# tx_board.net
KiCad netlist of a schematic drawn in EAGLE
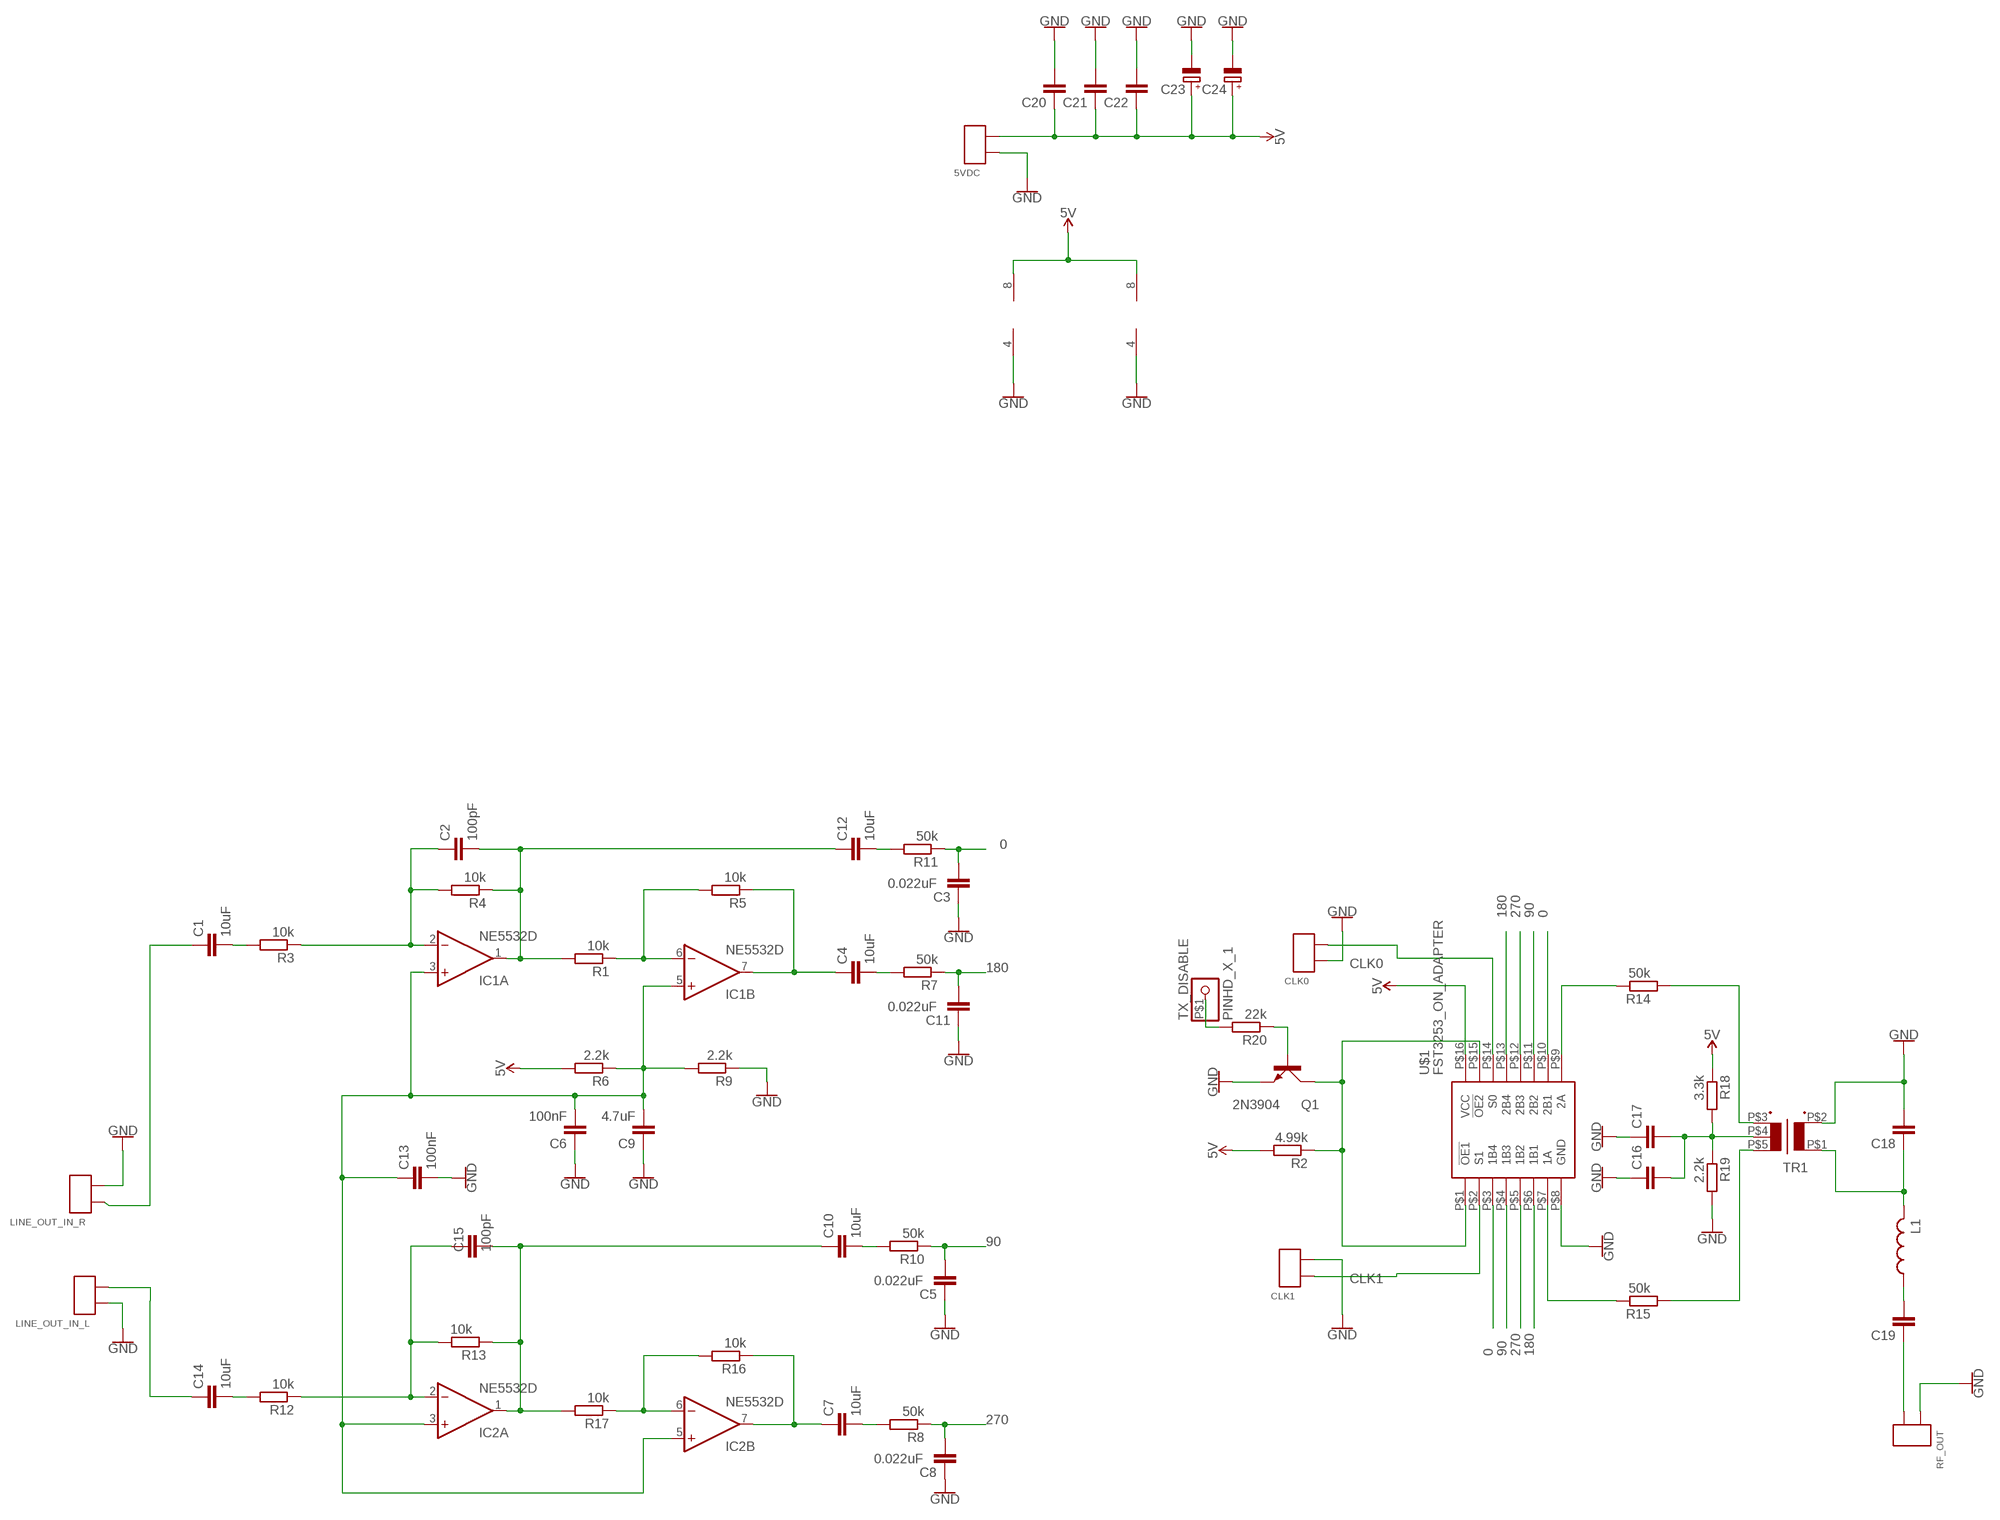
[diagram p0: schematic, sheet 1]

(export (version "E")
  (design (tool "Eeschema 10.0.6"))
  (components
    (comp (ref "5VDC")
      (value "2X_SMD_PTH_PIN")
      (footprint "eagle-import:2X_SMD_PTH")
      (libsource (lib "eagle-import") (part "2X_SMD_PTH_PIN"))
    )
    (comp (ref "C1")
      (value "10uF")
      (footprint "eagle-import:C0805K")
      (libsource (lib "eagle-import") (part "C_0805_PTH"))
    )
    (comp (ref "C2")
      (value "100pF")
      (footprint "eagle-import:C0805K")
      (libsource (lib "eagle-import") (part "C_0805_PTH"))
    )
    (comp (ref "C3")
      (value "0.022uF")
      (footprint "eagle-import:C0805")
      (libsource (lib "eagle-import") (part "C_0805_SMD"))
    )
    (comp (ref "C4")
      (value "10uF")
      (footprint "eagle-import:C0805K")
      (libsource (lib "eagle-import") (part "C_0805_PTH"))
    )
    (comp (ref "C5")
      (value "0.022uF")
      (footprint "eagle-import:C0805")
      (libsource (lib "eagle-import") (part "C_0805_SMD"))
    )
    (comp (ref "C6")
      (value "100nF")
      (footprint "eagle-import:C0805")
      (libsource (lib "eagle-import") (part "C_0805_SMD"))
    )
    (comp (ref "C7")
      (value "10uF")
      (footprint "eagle-import:C0805K")
      (libsource (lib "eagle-import") (part "C_0805_PTH"))
    )
    (comp (ref "C8")
      (value "0.022uF")
      (footprint "eagle-import:C0805")
      (libsource (lib "eagle-import") (part "C_0805_SMD"))
    )
    (comp (ref "C9")
      (value "4.7uF")
      (footprint "eagle-import:C0805")
      (libsource (lib "eagle-import") (part "C_0805_SMD"))
    )
    (comp (ref "C10")
      (value "10uF")
      (footprint "eagle-import:C0805K")
      (libsource (lib "eagle-import") (part "C_0805_PTH"))
    )
    (comp (ref "C11")
      (value "0.022uF")
      (footprint "eagle-import:C0805")
      (libsource (lib "eagle-import") (part "C_0805_SMD"))
    )
    (comp (ref "C12")
      (value "10uF")
      (footprint "eagle-import:C0805K")
      (libsource (lib "eagle-import") (part "C_0805_PTH"))
    )
    (comp (ref "C13")
      (value "100nF")
      (footprint "eagle-import:C0805")
      (libsource (lib "eagle-import") (part "C_0805_SMD"))
    )
    (comp (ref "C14")
      (value "10uF")
      (footprint "eagle-import:C0805K")
      (libsource (lib "eagle-import") (part "C_0805_PTH"))
    )
    (comp (ref "C15")
      (value "100pF")
      (footprint "eagle-import:C0805K")
      (libsource (lib "eagle-import") (part "C_0805_PTH"))
    )
    (comp (ref "C16")
      (value "C_0805_SMD")
      (footprint "eagle-import:C0805")
      (libsource (lib "eagle-import") (part "C_0805_SMD"))
    )
    (comp (ref "C17")
      (value "C_0805_PTH")
      (footprint "eagle-import:C0805K")
      (libsource (lib "eagle-import") (part "C_0805_PTH"))
    )
    (comp (ref "C18")
      (value "C_0805_PTH")
      (footprint "eagle-import:C0805K")
      (libsource (lib "eagle-import") (part "C_0805_PTH"))
    )
    (comp (ref "C19")
      (value "C_0805_PTH")
      (footprint "eagle-import:C0805K")
      (libsource (lib "eagle-import") (part "C_0805_PTH"))
    )
    (comp (ref "C20")
      (value "C_0805_SMD")
      (footprint "eagle-import:C0805")
      (libsource (lib "eagle-import") (part "C_0805_SMD"))
    )
    (comp (ref "C21")
      (value "C_0805_SMD")
      (footprint "eagle-import:C0805")
      (libsource (lib "eagle-import") (part "C_0805_SMD"))
    )
    (comp (ref "C22")
      (value "C_0805_SMD")
      (footprint "eagle-import:C0805")
      (libsource (lib "eagle-import") (part "C_0805_SMD"))
    )
    (comp (ref "C23")
      (value "C_POL")
      (footprint "eagle-import:E5-5")
      (libsource (lib "eagle-import") (part "C_POL"))
    )
    (comp (ref "C24")
      (value "C_POL")
      (footprint "eagle-import:E5-5")
      (libsource (lib "eagle-import") (part "C_POL"))
    )
    (comp (ref "CLK0")
      (value "2X_SMD_PTH_PIN")
      (footprint "eagle-import:2X_SMD_PTH")
      (libsource (lib "eagle-import") (part "2X_SMD_PTH_PIN"))
    )
    (comp (ref "CLK1")
      (value "2X_SMD_PTH_PIN")
      (footprint "eagle-import:2X_SMD_PTH")
      (libsource (lib "eagle-import") (part "2X_SMD_PTH_PIN"))
    )
    (comp (ref "IC1")
      (value "NE5532D")
      (footprint "eagle-import:SO08")
      (libsource (lib "eagle-import") (part "NE5532D"))
    )
    (comp (ref "IC2")
      (value "NE5532D")
      (footprint "eagle-import:SO08")
      (libsource (lib "eagle-import") (part "NE5532D"))
    )
    (comp (ref "L1")
      (value "L_0805_PTH")
      (footprint "eagle-import:M0805")
      (libsource (lib "eagle-import") (part "L_0805_PTH"))
    )
    (comp (ref "LINE_OUT_IN_L")
      (value "2X_SMD_PTH_PIN")
      (footprint "eagle-import:2X_SMD_PTH")
      (libsource (lib "eagle-import") (part "2X_SMD_PTH_PIN"))
    )
    (comp (ref "LINE_OUT_IN_R")
      (value "2X_SMD_PTH_PIN")
      (footprint "eagle-import:2X_SMD_PTH")
      (libsource (lib "eagle-import") (part "2X_SMD_PTH_PIN"))
    )
    (comp (ref "Q1")
      (value "2N3904")
      (footprint "eagle-import:TO92D")
      (libsource (lib "eagle-import") (part "2N3904"))
    )
    (comp (ref "R1")
      (value "10k")
      (footprint "eagle-import:R0805")
      (libsource (lib "eagle-import") (part "R_0805_PTH"))
    )
    (comp (ref "R2")
      (value "4.99k")
      (footprint "eagle-import:R0805W")
      (libsource (lib "eagle-import") (part "R_0805_SMD"))
    )
    (comp (ref "R3")
      (value "10k")
      (footprint "eagle-import:R0805")
      (libsource (lib "eagle-import") (part "R_0805_PTH"))
    )
    (comp (ref "R4")
      (value "10k")
      (footprint "eagle-import:R0805")
      (libsource (lib "eagle-import") (part "R_0805_PTH"))
    )
    (comp (ref "R5")
      (value "10k")
      (footprint "eagle-import:R0805W")
      (libsource (lib "eagle-import") (part "R_0805_SMD"))
    )
    (comp (ref "R6")
      (value "2.2k")
      (footprint "eagle-import:0204_7")
      (libsource (lib "eagle-import") (part "R-EU_0204/7"))
    )
    (comp (ref "R7")
      (value "50k")
      (footprint "eagle-import:R0805")
      (libsource (lib "eagle-import") (part "R_0805_PTH"))
    )
    (comp (ref "R8")
      (value "50k")
      (footprint "eagle-import:R0805")
      (libsource (lib "eagle-import") (part "R_0805_PTH"))
    )
    (comp (ref "R9")
      (value "2.2k")
      (footprint "eagle-import:R0805W")
      (libsource (lib "eagle-import") (part "R_0805_SMD"))
    )
    (comp (ref "R10")
      (value "50k")
      (footprint "eagle-import:R0805")
      (libsource (lib "eagle-import") (part "R_0805_PTH"))
    )
    (comp (ref "R11")
      (value "50k")
      (footprint "eagle-import:R0805")
      (libsource (lib "eagle-import") (part "R_0805_PTH"))
    )
    (comp (ref "R12")
      (value "10k")
      (footprint "eagle-import:R0805")
      (libsource (lib "eagle-import") (part "R_0805_PTH"))
    )
    (comp (ref "R13")
      (value "10k")
      (footprint "eagle-import:R0805")
      (libsource (lib "eagle-import") (part "R_0805_PTH"))
    )
    (comp (ref "R14")
      (value "50k")
      (footprint "eagle-import:R0805")
      (libsource (lib "eagle-import") (part "R_0805_PTH"))
    )
    (comp (ref "R15")
      (value "50k")
      (footprint "eagle-import:R0805")
      (libsource (lib "eagle-import") (part "R_0805_PTH"))
    )
    (comp (ref "R16")
      (value "10k")
      (footprint "eagle-import:R0805")
      (libsource (lib "eagle-import") (part "R_0805_PTH"))
    )
    (comp (ref "R17")
      (value "10k")
      (footprint "eagle-import:R0805W")
      (libsource (lib "eagle-import") (part "R_0805_SMD"))
    )
    (comp (ref "R18")
      (value "3.3k")
      (footprint "eagle-import:R0805W")
      (libsource (lib "eagle-import") (part "R_0805_SMD"))
    )
    (comp (ref "R19")
      (value "2.2k")
      (footprint "eagle-import:R0805W")
      (libsource (lib "eagle-import") (part "R_0805_SMD"))
    )
    (comp (ref "R20")
      (value "22k")
      (footprint "eagle-import:R0805W")
      (libsource (lib "eagle-import") (part "R_0805_SMD"))
    )
    (comp (ref "RF_OUT")
      (value "2X_SMD_PTH_PIN")
      (footprint "eagle-import:2X_SMD_PTH")
      (libsource (lib "eagle-import") (part "2X_SMD_PTH_PIN"))
    )
    (comp (ref "TR1")
      (value "5PIN_TRANSFORMER")
      (footprint "eagle-import:5PIN_TRANSFORMER")
      (libsource (lib "eagle-import") (part "5PIN_TRANSFORMER"))
    )
    (comp (ref "TX_DISABLE")
      (value "PINHD_X_1")
      (footprint "eagle-import:PINHD1")
      (libsource (lib "eagle-import") (part "PINHD_X_1"))
    )
    (comp (ref "U$1")
      (value "FST3253_ON_ADAPTER")
      (footprint "eagle-import:SSOP16_ADAPTER")
      (libsource (lib "eagle-import") (part "FST3253_ON_ADAPTER"))
    )
  )
  (nets
    (net (code "1") (name "/0") (class "Default")
      (node (ref "C3") (pin "2") (pinfunction "2_2") (pintype "passive"))
      (node (ref "R11") (pin "1") (pinfunction "1_1") (pintype "passive"))
      (node (ref "R11") (pin "P$1") (pinfunction "1_P$1") (pintype "passive"))
      (node (ref "U$1") (pin "P$10") (pinfunction "2B1_P$10") (pintype "bidirectional"))
      (node (ref "U$1") (pin "P$3") (pinfunction "1B4_P$3") (pintype "bidirectional"))
    )
    (net (code "2") (name "/90") (class "Default")
      (node (ref "C5") (pin "2") (pinfunction "2_2") (pintype "passive"))
      (node (ref "R10") (pin "1") (pinfunction "1_1") (pintype "passive"))
      (node (ref "R10") (pin "P$1") (pinfunction "1_P$1") (pintype "passive"))
      (node (ref "U$1") (pin "P$11") (pinfunction "2B2_P$11") (pintype "bidirectional"))
      (node (ref "U$1") (pin "P$4") (pinfunction "1B3_P$4") (pintype "bidirectional"))
    )
    (net (code "3") (name "/180") (class "Default")
      (node (ref "C11") (pin "2") (pinfunction "2_2") (pintype "passive"))
      (node (ref "R7") (pin "1") (pinfunction "1_1") (pintype "passive"))
      (node (ref "R7") (pin "P$1") (pinfunction "1_P$1") (pintype "passive"))
      (node (ref "U$1") (pin "P$13") (pinfunction "2B4_P$13") (pintype "bidirectional"))
      (node (ref "U$1") (pin "P$6") (pinfunction "1B1_P$6") (pintype "bidirectional"))
    )
    (net (code "4") (name "/270") (class "Default")
      (node (ref "C8") (pin "2") (pinfunction "2_2") (pintype "passive"))
      (node (ref "R8") (pin "1") (pinfunction "1_1") (pintype "passive"))
      (node (ref "R8") (pin "P$1") (pinfunction "1_P$1") (pintype "passive"))
      (node (ref "U$1") (pin "P$12") (pinfunction "2B3_P$12") (pintype "bidirectional"))
      (node (ref "U$1") (pin "P$5") (pinfunction "1B2_P$5") (pintype "bidirectional"))
    )
    (net (code "5") (name "/CLK0") (class "Default")
      (node (ref "CLK0") (pin "P$2") (pinfunction "PIN1_P$2") (pintype "bidirectional"))
      (node (ref "CLK0") (pin "T$2") (pinfunction "PIN1_T$2") (pintype "bidirectional"))
      (node (ref "U$1") (pin "P$14") (pinfunction "S0_P$14") (pintype "bidirectional"))
    )
    (net (code "6") (name "/CLK1") (class "Default")
      (node (ref "CLK1") (pin "P$1") (pinfunction "PIN0_P$1") (pintype "bidirectional"))
      (node (ref "CLK1") (pin "T$1") (pinfunction "PIN0_T$1") (pintype "bidirectional"))
      (node (ref "U$1") (pin "P$2") (pinfunction "S1_P$2") (pintype "bidirectional"))
    )
    (net (code "7") (name "5V") (class "Default")
      (node (ref "5VDC") (pin "P$2") (pinfunction "PIN1_P$2") (pintype "bidirectional"))
      (node (ref "5VDC") (pin "T$2") (pinfunction "PIN1_T$2") (pintype "bidirectional"))
      (node (ref "C20") (pin "1") (pinfunction "1_1") (pintype "passive"))
      (node (ref "C21") (pin "1") (pinfunction "1_1") (pintype "passive"))
      (node (ref "C22") (pin "1") (pinfunction "1_1") (pintype "passive"))
      (node (ref "C23") (pin "+") (pinfunction "+_+") (pintype "passive"))
      (node (ref "C24") (pin "+") (pinfunction "+_+") (pintype "passive"))
      (node (ref "IC1") (pin "8") (pinfunction "V+_8") (pintype "power_in"))
      (node (ref "IC2") (pin "8") (pinfunction "V+_8") (pintype "power_in"))
      (node (ref "R18") (pin "1") (pinfunction "1_1") (pintype "passive"))
      (node (ref "R2") (pin "2") (pinfunction "2_2") (pintype "passive"))
      (node (ref "R6") (pin "2") (pinfunction "2_2") (pintype "passive"))
      (node (ref "U$1") (pin "P$16") (pinfunction "VCC_P$16") (pintype "power_in"))
    )
    (net (code "8") (name "GND") (class "Default")
      (node (ref "5VDC") (pin "P$1") (pinfunction "PIN0_P$1") (pintype "bidirectional"))
      (node (ref "5VDC") (pin "T$1") (pinfunction "PIN0_T$1") (pintype "bidirectional"))
      (node (ref "C11") (pin "1") (pinfunction "1_1") (pintype "passive"))
      (node (ref "C13") (pin "2") (pinfunction "2_2") (pintype "passive"))
      (node (ref "C16") (pin "1") (pinfunction "1_1") (pintype "passive"))
      (node (ref "C17") (pin "1") (pinfunction "1_1") (pintype "passive"))
      (node (ref "C17") (pin "P$1") (pinfunction "1_P$1") (pintype "passive"))
      (node (ref "C18") (pin "2") (pinfunction "2_2") (pintype "passive"))
      (node (ref "C18") (pin "P$2") (pinfunction "2_P$2") (pintype "passive"))
      (node (ref "C20") (pin "2") (pinfunction "2_2") (pintype "passive"))
      (node (ref "C21") (pin "2") (pinfunction "2_2") (pintype "passive"))
      (node (ref "C22") (pin "2") (pinfunction "2_2") (pintype "passive"))
      (node (ref "C23") (pin "-") (pinfunction "-_-") (pintype "passive"))
      (node (ref "C24") (pin "-") (pinfunction "-_-") (pintype "passive"))
      (node (ref "C3") (pin "1") (pinfunction "1_1") (pintype "passive"))
      (node (ref "C5") (pin "1") (pinfunction "1_1") (pintype "passive"))
      (node (ref "C6") (pin "1") (pinfunction "1_1") (pintype "passive"))
      (node (ref "C8") (pin "1") (pinfunction "1_1") (pintype "passive"))
      (node (ref "C9") (pin "1") (pinfunction "1_1") (pintype "passive"))
      (node (ref "CLK0") (pin "P$1") (pinfunction "PIN0_P$1") (pintype "bidirectional"))
      (node (ref "CLK0") (pin "T$1") (pinfunction "PIN0_T$1") (pintype "bidirectional"))
      (node (ref "CLK1") (pin "P$2") (pinfunction "PIN1_P$2") (pintype "bidirectional"))
      (node (ref "CLK1") (pin "T$2") (pinfunction "PIN1_T$2") (pintype "bidirectional"))
      (node (ref "IC1") (pin "4") (pinfunction "V-_4") (pintype "power_in"))
      (node (ref "IC2") (pin "4") (pinfunction "V-_4") (pintype "power_in"))
      (node (ref "LINE_OUT_IN_L") (pin "P$1") (pinfunction "PIN0_P$1") (pintype "bidirectional"))
      (node (ref "LINE_OUT_IN_L") (pin "T$1") (pinfunction "PIN0_T$1") (pintype "bidirectional"))
      (node (ref "LINE_OUT_IN_R") (pin "P$2") (pinfunction "PIN1_P$2") (pintype "bidirectional"))
      (node (ref "LINE_OUT_IN_R") (pin "T$2") (pinfunction "PIN1_T$2") (pintype "bidirectional"))
      (node (ref "Q1") (pin "E") (pinfunction "E_E") (pintype "passive"))
      (node (ref "R19") (pin "2") (pinfunction "2_2") (pintype "passive"))
      (node (ref "R9") (pin "1") (pinfunction "1_1") (pintype "passive"))
      (node (ref "RF_OUT") (pin "P$1") (pinfunction "PIN0_P$1") (pintype "bidirectional"))
      (node (ref "RF_OUT") (pin "T$1") (pinfunction "PIN0_T$1") (pintype "bidirectional"))
      (node (ref "TR1") (pin "P$2") (pinfunction "2_P$2") (pintype "passive"))
      (node (ref "U$1") (pin "P$8") (pinfunction "GND_P$8") (pintype "power_in"))
    )
    (net (code "9") (name "Net-(C1-1-PadP$1)") (class "Default")
      (node (ref "C1") (pin "1") (pinfunction "1_1") (pintype "passive"))
      (node (ref "C1") (pin "P$1") (pinfunction "1_P$1") (pintype "passive"))
      (node (ref "LINE_OUT_IN_R") (pin "P$1") (pinfunction "PIN0_P$1") (pintype "bidirectional"))
      (node (ref "LINE_OUT_IN_R") (pin "T$1") (pinfunction "PIN0_T$1") (pintype "bidirectional"))
    )
    (net (code "10") (name "Net-(C1-2-PadP$2)") (class "Default")
      (node (ref "C1") (pin "2") (pinfunction "2_2") (pintype "passive"))
      (node (ref "C1") (pin "P$2") (pinfunction "2_P$2") (pintype "passive"))
      (node (ref "R3") (pin "2") (pinfunction "2_2") (pintype "passive"))
      (node (ref "R3") (pin "P$2") (pinfunction "2_P$2") (pintype "passive"))
    )
    (net (code "11") (name "Net-(C4-2-PadP$2)") (class "Default")
      (node (ref "C4") (pin "2") (pinfunction "2_2") (pintype "passive"))
      (node (ref "C4") (pin "P$2") (pinfunction "2_P$2") (pintype "passive"))
      (node (ref "R7") (pin "2") (pinfunction "2_2") (pintype "passive"))
      (node (ref "R7") (pin "P$2") (pinfunction "2_P$2") (pintype "passive"))
    )
    (net (code "12") (name "Net-(C7-2-PadP$2)") (class "Default")
      (node (ref "C7") (pin "2") (pinfunction "2_2") (pintype "passive"))
      (node (ref "C7") (pin "P$2") (pinfunction "2_P$2") (pintype "passive"))
      (node (ref "R8") (pin "2") (pinfunction "2_2") (pintype "passive"))
      (node (ref "R8") (pin "P$2") (pinfunction "2_P$2") (pintype "passive"))
    )
    (net (code "13") (name "Net-(C10-2-PadP$2)") (class "Default")
      (node (ref "C10") (pin "2") (pinfunction "2_2") (pintype "passive"))
      (node (ref "C10") (pin "P$2") (pinfunction "2_P$2") (pintype "passive"))
      (node (ref "R10") (pin "2") (pinfunction "2_2") (pintype "passive"))
      (node (ref "R10") (pin "P$2") (pinfunction "2_P$2") (pintype "passive"))
    )
    (net (code "14") (name "Net-(C12-2-PadP$2)") (class "Default")
      (node (ref "C12") (pin "2") (pinfunction "2_2") (pintype "passive"))
      (node (ref "C12") (pin "P$2") (pinfunction "2_P$2") (pintype "passive"))
      (node (ref "R11") (pin "2") (pinfunction "2_2") (pintype "passive"))
      (node (ref "R11") (pin "P$2") (pinfunction "2_P$2") (pintype "passive"))
    )
    (net (code "15") (name "Net-(C14-1-PadP$1)") (class "Default")
      (node (ref "C14") (pin "1") (pinfunction "1_1") (pintype "passive"))
      (node (ref "C14") (pin "P$1") (pinfunction "1_P$1") (pintype "passive"))
      (node (ref "LINE_OUT_IN_L") (pin "P$2") (pinfunction "PIN1_P$2") (pintype "bidirectional"))
      (node (ref "LINE_OUT_IN_L") (pin "T$2") (pinfunction "PIN1_T$2") (pintype "bidirectional"))
    )
    (net (code "16") (name "Net-(C14-2-PadP$2)") (class "Default")
      (node (ref "C14") (pin "2") (pinfunction "2_2") (pintype "passive"))
      (node (ref "C14") (pin "P$2") (pinfunction "2_P$2") (pintype "passive"))
      (node (ref "R12") (pin "2") (pinfunction "2_2") (pintype "passive"))
      (node (ref "R12") (pin "P$2") (pinfunction "2_P$2") (pintype "passive"))
    )
    (net (code "17") (name "Net-(C19-1-PadP$1)") (class "Default")
      (node (ref "C19") (pin "1") (pinfunction "1_1") (pintype "passive"))
      (node (ref "C19") (pin "P$1") (pinfunction "1_P$1") (pintype "passive"))
      (node (ref "RF_OUT") (pin "P$2") (pinfunction "PIN1_P$2") (pintype "bidirectional"))
      (node (ref "RF_OUT") (pin "T$2") (pinfunction "PIN1_T$2") (pintype "bidirectional"))
    )
    (net (code "18") (name "Net-(C19-2-PadP$2)") (class "Default")
      (node (ref "C19") (pin "2") (pinfunction "2_2") (pintype "passive"))
      (node (ref "C19") (pin "P$2") (pinfunction "2_P$2") (pintype "passive"))
      (node (ref "L1") (pin "1") (pinfunction "1_1") (pintype "passive"))
      (node (ref "L1") (pin "P$1") (pinfunction "1_P$1") (pintype "passive"))
    )
    (net (code "19") (name "Net-(IC1A-+IN)") (class "Default")
      (node (ref "C13") (pin "1") (pinfunction "1_1") (pintype "passive"))
      (node (ref "C6") (pin "2") (pinfunction "2_2") (pintype "passive"))
      (node (ref "C9") (pin "2") (pinfunction "2_2") (pintype "passive"))
      (node (ref "IC1") (pin "3") (pinfunction "+IN_3") (pintype "input"))
      (node (ref "IC1") (pin "5") (pinfunction "+IN_5") (pintype "input"))
      (node (ref "IC2") (pin "3") (pinfunction "+IN_3") (pintype "input"))
      (node (ref "IC2") (pin "5") (pinfunction "+IN_5") (pintype "input"))
      (node (ref "R6") (pin "1") (pinfunction "1_1") (pintype "passive"))
      (node (ref "R9") (pin "2") (pinfunction "2_2") (pintype "passive"))
    )
    (net (code "20") (name "Net-(IC1A--IN)") (class "Default")
      (node (ref "C2") (pin "1") (pinfunction "1_1") (pintype "passive"))
      (node (ref "C2") (pin "P$1") (pinfunction "1_P$1") (pintype "passive"))
      (node (ref "IC1") (pin "2") (pinfunction "-IN_2") (pintype "input"))
      (node (ref "R3") (pin "1") (pinfunction "1_1") (pintype "passive"))
      (node (ref "R3") (pin "P$1") (pinfunction "1_P$1") (pintype "passive"))
      (node (ref "R4") (pin "2") (pinfunction "2_2") (pintype "passive"))
      (node (ref "R4") (pin "P$2") (pinfunction "2_P$2") (pintype "passive"))
    )
    (net (code "21") (name "Net-(IC1A-OUT)") (class "Default")
      (node (ref "C12") (pin "1") (pinfunction "1_1") (pintype "passive"))
      (node (ref "C12") (pin "P$1") (pinfunction "1_P$1") (pintype "passive"))
      (node (ref "C2") (pin "2") (pinfunction "2_2") (pintype "passive"))
      (node (ref "C2") (pin "P$2") (pinfunction "2_P$2") (pintype "passive"))
      (node (ref "IC1") (pin "1") (pinfunction "OUT_1") (pintype "output"))
      (node (ref "R1") (pin "2") (pinfunction "2_2") (pintype "passive"))
      (node (ref "R1") (pin "P$2") (pinfunction "2_P$2") (pintype "passive"))
      (node (ref "R4") (pin "1") (pinfunction "1_1") (pintype "passive"))
      (node (ref "R4") (pin "P$1") (pinfunction "1_P$1") (pintype "passive"))
    )
    (net (code "22") (name "Net-(IC1B--IN)") (class "Default")
      (node (ref "IC1") (pin "6") (pinfunction "-IN_6") (pintype "input"))
      (node (ref "R1") (pin "1") (pinfunction "1_1") (pintype "passive"))
      (node (ref "R1") (pin "P$1") (pinfunction "1_P$1") (pintype "passive"))
      (node (ref "R5") (pin "2") (pinfunction "2_2") (pintype "passive"))
    )
    (net (code "23") (name "Net-(IC1B-OUT)") (class "Default")
      (node (ref "C4") (pin "1") (pinfunction "1_1") (pintype "passive"))
      (node (ref "C4") (pin "P$1") (pinfunction "1_P$1") (pintype "passive"))
      (node (ref "IC1") (pin "7") (pinfunction "OUT_7") (pintype "output"))
      (node (ref "R5") (pin "1") (pinfunction "1_1") (pintype "passive"))
    )
    (net (code "24") (name "Net-(IC2A--IN)") (class "Default")
      (node (ref "C15") (pin "1") (pinfunction "1_1") (pintype "passive"))
      (node (ref "C15") (pin "P$1") (pinfunction "1_P$1") (pintype "passive"))
      (node (ref "IC2") (pin "2") (pinfunction "-IN_2") (pintype "input"))
      (node (ref "R12") (pin "1") (pinfunction "1_1") (pintype "passive"))
      (node (ref "R12") (pin "P$1") (pinfunction "1_P$1") (pintype "passive"))
      (node (ref "R13") (pin "2") (pinfunction "2_2") (pintype "passive"))
      (node (ref "R13") (pin "P$2") (pinfunction "2_P$2") (pintype "passive"))
    )
    (net (code "25") (name "Net-(IC2A-OUT)") (class "Default")
      (node (ref "C10") (pin "1") (pinfunction "1_1") (pintype "passive"))
      (node (ref "C10") (pin "P$1") (pinfunction "1_P$1") (pintype "passive"))
      (node (ref "C15") (pin "2") (pinfunction "2_2") (pintype "passive"))
      (node (ref "C15") (pin "P$2") (pinfunction "2_P$2") (pintype "passive"))
      (node (ref "IC2") (pin "1") (pinfunction "OUT_1") (pintype "output"))
      (node (ref "R13") (pin "1") (pinfunction "1_1") (pintype "passive"))
      (node (ref "R13") (pin "P$1") (pinfunction "1_P$1") (pintype "passive"))
      (node (ref "R17") (pin "2") (pinfunction "2_2") (pintype "passive"))
    )
    (net (code "26") (name "Net-(IC2B--IN)") (class "Default")
      (node (ref "IC2") (pin "6") (pinfunction "-IN_6") (pintype "input"))
      (node (ref "R16") (pin "2") (pinfunction "2_2") (pintype "passive"))
      (node (ref "R16") (pin "P$2") (pinfunction "2_P$2") (pintype "passive"))
      (node (ref "R17") (pin "1") (pinfunction "1_1") (pintype "passive"))
    )
    (net (code "27") (name "Net-(IC2B-OUT)") (class "Default")
      (node (ref "C7") (pin "1") (pinfunction "1_1") (pintype "passive"))
      (node (ref "C7") (pin "P$1") (pinfunction "1_P$1") (pintype "passive"))
      (node (ref "IC2") (pin "7") (pinfunction "OUT_7") (pintype "output"))
      (node (ref "R16") (pin "1") (pinfunction "1_1") (pintype "passive"))
      (node (ref "R16") (pin "P$1") (pinfunction "1_P$1") (pintype "passive"))
    )
    (net (code "28") (name "Net-(Q1-PadB)") (class "Default")
      (node (ref "Q1") (pin "B") (pinfunction "B_B") (pintype "passive"))
      (node (ref "R20") (pin "1") (pinfunction "1_1") (pintype "passive"))
    )
    (net (code "29") (name "Net-(TR1-1)") (class "Default")
      (node (ref "C18") (pin "1") (pinfunction "1_1") (pintype "passive"))
      (node (ref "C18") (pin "P$1") (pinfunction "1_P$1") (pintype "passive"))
      (node (ref "L1") (pin "2") (pinfunction "2_2") (pintype "passive"))
      (node (ref "L1") (pin "P$2") (pinfunction "2_P$2") (pintype "passive"))
      (node (ref "TR1") (pin "P$1") (pinfunction "1_P$1") (pintype "passive"))
    )
    (net (code "30") (name "Net-(TR1-3)") (class "Default")
      (node (ref "R14") (pin "1") (pinfunction "1_1") (pintype "passive"))
      (node (ref "R14") (pin "P$1") (pinfunction "1_P$1") (pintype "passive"))
      (node (ref "TR1") (pin "P$3") (pinfunction "3_P$3") (pintype "passive"))
    )
    (net (code "31") (name "Net-(TR1-4)") (class "Default")
      (node (ref "C16") (pin "2") (pinfunction "2_2") (pintype "passive"))
      (node (ref "C17") (pin "2") (pinfunction "2_2") (pintype "passive"))
      (node (ref "C17") (pin "P$2") (pinfunction "2_P$2") (pintype "passive"))
      (node (ref "R18") (pin "2") (pinfunction "2_2") (pintype "passive"))
      (node (ref "R19") (pin "1") (pinfunction "1_1") (pintype "passive"))
      (node (ref "TR1") (pin "P$4") (pinfunction "4_P$4") (pintype "passive"))
    )
    (net (code "32") (name "Net-(TR1-5)") (class "Default")
      (node (ref "R15") (pin "1") (pinfunction "1_1") (pintype "passive"))
      (node (ref "R15") (pin "P$1") (pinfunction "1_P$1") (pintype "passive"))
      (node (ref "TR1") (pin "P$5") (pinfunction "5_P$5") (pintype "passive"))
    )
    (net (code "33") (name "Net-(TX_DISABLE-1)") (class "Default")
      (node (ref "R20") (pin "2") (pinfunction "2_2") (pintype "passive"))
      (node (ref "TX_DISABLE") (pin "P$1") (pinfunction "1_P$1") (pintype "passive"))
    )
    (net (code "34") (name "Net-(U$1-1A)") (class "Default")
      (node (ref "R15") (pin "2") (pinfunction "2_2") (pintype "passive"))
      (node (ref "R15") (pin "P$2") (pinfunction "2_P$2") (pintype "passive"))
      (node (ref "U$1") (pin "P$7") (pinfunction "1A_P$7") (pintype "bidirectional"))
    )
    (net (code "35") (name "Net-(U$1-2A)") (class "Default")
      (node (ref "R14") (pin "2") (pinfunction "2_2") (pintype "passive"))
      (node (ref "R14") (pin "P$2") (pinfunction "2_P$2") (pintype "passive"))
      (node (ref "U$1") (pin "P$9") (pinfunction "2A_P$9") (pintype "bidirectional"))
    )
    (net (code "36") (name "Net-(U$1-~{OE1})") (class "Default")
      (node (ref "Q1") (pin "C") (pinfunction "C_C") (pintype "passive"))
      (node (ref "R2") (pin "1") (pinfunction "1_1") (pintype "passive"))
      (node (ref "U$1") (pin "P$1") (pinfunction "~{OE1}_P$1") (pintype "bidirectional"))
      (node (ref "U$1") (pin "P$15") (pinfunction "~{OE2}_P$15") (pintype "bidirectional"))
    )
  )
)
